# 555_project_555timer_ic_revA.net
KiCad netlist of a schematic drawn in EAGLE
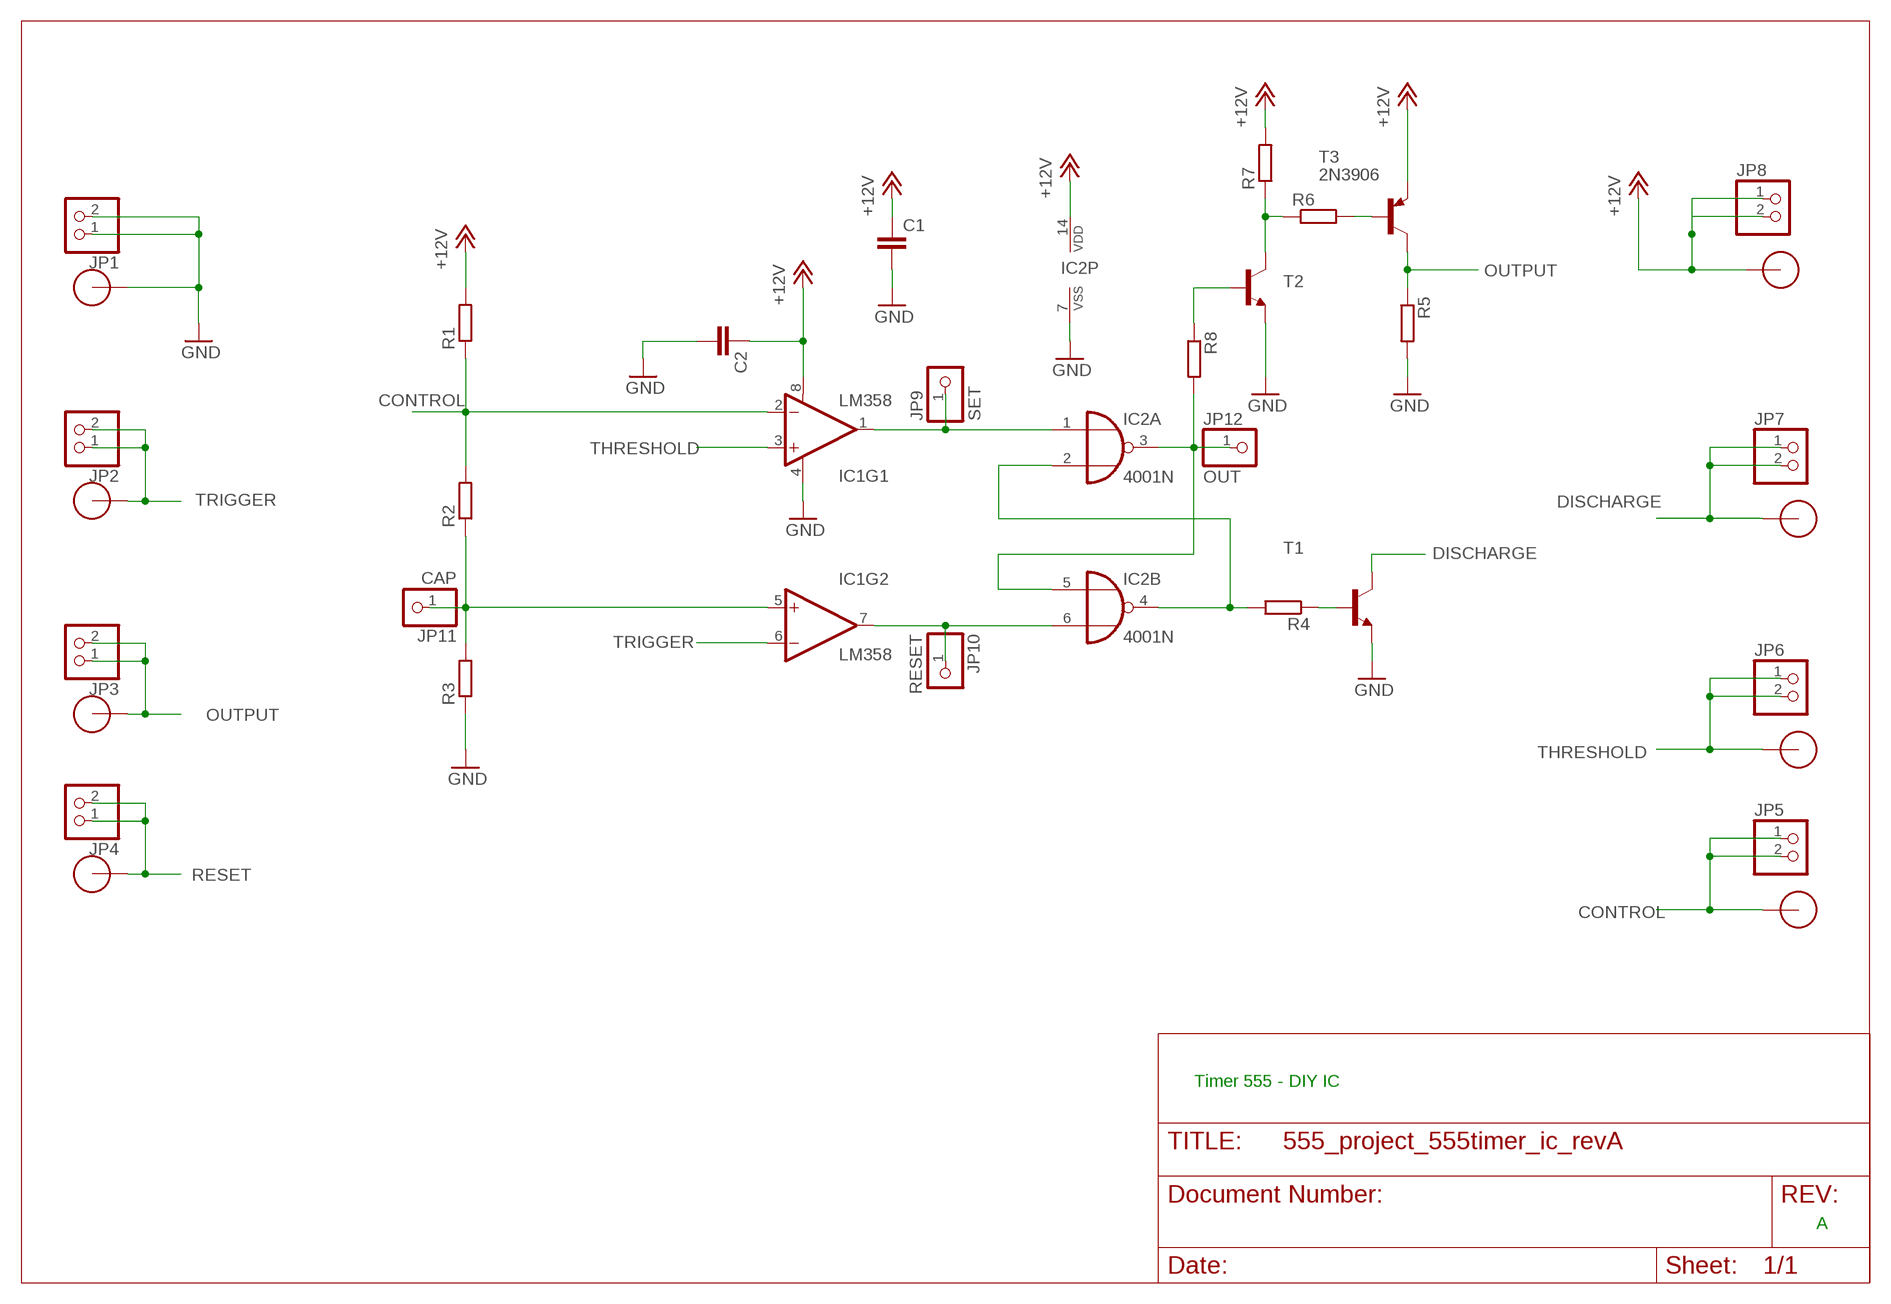
[diagram p0: schematic, sheet 1]

(export (version "E")
  (design (tool "Eeschema 10.0.6"))
  (components
    (comp (ref "C1")
      (value "C-EU025-024X044")
      (footprint "eagle-import:C025-024X044")
      (libsource (lib "eagle-import") (part "C-EU025-024X044"))
    )
    (comp (ref "C2")
      (value "C-EU025-024X044")
      (footprint "eagle-import:C025-024X044")
      (libsource (lib "eagle-import") (part "C-EU025-024X044"))
    )
    (comp (ref "IC1")
      (value "LM358")
      (footprint "eagle-import:DIP08")
      (libsource (lib "eagle-import") (part "LM358"))
    )
    (comp (ref "IC2")
      (value "4001N")
      (footprint "eagle-import:DIL14")
      (libsource (lib "eagle-import") (part "4001N"))
    )
    (comp (ref "JP1")
      (value "PINHD-1X2")
      (footprint "eagle-import:1X02")
      (libsource (lib "eagle-import") (part "PINHD-1X2"))
    )
    (comp (ref "JP2")
      (value "PINHD-1X2")
      (footprint "eagle-import:1X02")
      (libsource (lib "eagle-import") (part "PINHD-1X2"))
    )
    (comp (ref "JP3")
      (value "PINHD-1X2")
      (footprint "eagle-import:1X02")
      (libsource (lib "eagle-import") (part "PINHD-1X2"))
    )
    (comp (ref "JP4")
      (value "PINHD-1X2")
      (footprint "eagle-import:1X02")
      (libsource (lib "eagle-import") (part "PINHD-1X2"))
    )
    (comp (ref "JP5")
      (value "PINHD-1X2")
      (footprint "eagle-import:1X02")
      (libsource (lib "eagle-import") (part "PINHD-1X2"))
    )
    (comp (ref "JP6")
      (value "PINHD-1X2")
      (footprint "eagle-import:1X02")
      (libsource (lib "eagle-import") (part "PINHD-1X2"))
    )
    (comp (ref "JP7")
      (value "PINHD-1X2")
      (footprint "eagle-import:1X02")
      (libsource (lib "eagle-import") (part "PINHD-1X2"))
    )
    (comp (ref "JP8")
      (value "PINHD-1X2")
      (footprint "eagle-import:1X02")
      (libsource (lib "eagle-import") (part "PINHD-1X2"))
    )
    (comp (ref "JP9")
      (value "SET")
      (footprint "eagle-import:1X01")
      (libsource (lib "eagle-import") (part "PINHD-1X1"))
    )
    (comp (ref "JP10")
      (value "RESET")
      (footprint "eagle-import:1X01")
      (libsource (lib "eagle-import") (part "PINHD-1X1"))
    )
    (comp (ref "JP11")
      (value "CAP")
      (footprint "eagle-import:1X01")
      (libsource (lib "eagle-import") (part "PINHD-1X1"))
    )
    (comp (ref "JP12")
      (value "OUT")
      (footprint "eagle-import:1X01")
      (libsource (lib "eagle-import") (part "PINHD-1X1"))
    )
    (comp (ref "R1")
      (value "R-EU_0204/7")
      (footprint "eagle-import:0204_7")
      (libsource (lib "eagle-import") (part "R-EU_0204/7"))
    )
    (comp (ref "R2")
      (value "R-EU_0204/7")
      (footprint "eagle-import:0204_7")
      (libsource (lib "eagle-import") (part "R-EU_0204/7"))
    )
    (comp (ref "R3")
      (value "R-EU_0204/7")
      (footprint "eagle-import:0204_7")
      (libsource (lib "eagle-import") (part "R-EU_0204/7"))
    )
    (comp (ref "R4")
      (value "R-EU_0204/7")
      (footprint "eagle-import:0204_7")
      (libsource (lib "eagle-import") (part "R-EU_0204/7"))
    )
    (comp (ref "R5")
      (value "R-EU_0204/7")
      (footprint "eagle-import:0204_7")
      (libsource (lib "eagle-import") (part "R-EU_0204/7"))
    )
    (comp (ref "R6")
      (value "R-EU_0204/7")
      (footprint "eagle-import:0204_7")
      (libsource (lib "eagle-import") (part "R-EU_0204/7"))
    )
    (comp (ref "R7")
      (value "R-EU_0204/7")
      (footprint "eagle-import:0204_7")
      (libsource (lib "eagle-import") (part "R-EU_0204/7"))
    )
    (comp (ref "R8")
      (value "R-EU_0204/7")
      (footprint "eagle-import:0204_7")
      (libsource (lib "eagle-import") (part "R-EU_0204/7"))
    )
    (comp (ref "T1")
      (value "BC546-NPN-TO92-CBE")
      (footprint "eagle-import:TO92-CBE")
      (libsource (lib "eagle-import") (part "-NPN-TO92-CBEBC546"))
    )
    (comp (ref "T2")
      (value "TRANSISTOR_NPN2N3904")
      (footprint "eagle-import:TO-92")
      (libsource (lib "eagle-import") (part "TRANSISTOR_NPN2N3904"))
    )
    (comp (ref "T3")
      (value "2N3906")
      (footprint "eagle-import:TO92")
      (libsource (lib "eagle-import") (part "2N3906"))
    )
    (comp (ref "U$1")
      (value "ALLIGATOR_CLIP_PAD")
      (footprint "eagle-import:BIGTAP")
      (libsource (lib "eagle-import") (part "ALLIGATOR_CLIP_PAD"))
    )
    (comp (ref "U$3")
      (value "ALLIGATOR_CLIP_PAD")
      (footprint "eagle-import:BIGTAP")
      (libsource (lib "eagle-import") (part "ALLIGATOR_CLIP_PAD"))
    )
    (comp (ref "U$4")
      (value "ALLIGATOR_CLIP_PAD")
      (footprint "eagle-import:BIGTAP")
      (libsource (lib "eagle-import") (part "ALLIGATOR_CLIP_PAD"))
    )
    (comp (ref "U$5")
      (value "ALLIGATOR_CLIP_PAD")
      (footprint "eagle-import:BIGTAP")
      (libsource (lib "eagle-import") (part "ALLIGATOR_CLIP_PAD"))
    )
    (comp (ref "U$6")
      (value "ALLIGATOR_CLIP_PAD")
      (footprint "eagle-import:BIGTAP")
      (libsource (lib "eagle-import") (part "ALLIGATOR_CLIP_PAD"))
    )
    (comp (ref "U$7")
      (value "ALLIGATOR_CLIP_PAD")
      (footprint "eagle-import:BIGTAP")
      (libsource (lib "eagle-import") (part "ALLIGATOR_CLIP_PAD"))
    )
    (comp (ref "U$8")
      (value "ALLIGATOR_CLIP_PAD")
      (footprint "eagle-import:BIGTAP")
      (libsource (lib "eagle-import") (part "ALLIGATOR_CLIP_PAD"))
    )
    (comp (ref "U$9")
      (value "ALLIGATOR_CLIP_PAD")
      (footprint "eagle-import:BIGTAP")
      (libsource (lib "eagle-import") (part "ALLIGATOR_CLIP_PAD"))
    )
  )
  (nets
    (net (code "1") (name "+12V") (class "Default")
      (node (ref "C1") (pin "1") (pinfunction "1_1") (pintype "passive"))
      (node (ref "C2") (pin "1") (pinfunction "1_1") (pintype "passive"))
      (node (ref "IC1") (pin "8") (pinfunction "V+_8") (pintype "power_in"))
      (node (ref "IC2") (pin "14") (pinfunction "VDD_14") (pintype "power_in"))
      (node (ref "JP8") (pin "1") (pinfunction "1_1") (pintype "passive"))
      (node (ref "JP8") (pin "2") (pinfunction "2_2") (pintype "passive"))
      (node (ref "R1") (pin "2") (pinfunction "2_2") (pintype "passive"))
      (node (ref "R7") (pin "2") (pinfunction "2_2") (pintype "passive"))
      (node (ref "T3") (pin "3") (pinfunction "E_3") (pintype "passive"))
      (node (ref "U$7") (pin "P$1") (pinfunction "P$1_P$1") (pintype "bidirectional"))
    )
    (net (code "2") (name "/CONTROL") (class "Default")
      (node (ref "IC1") (pin "2") (pinfunction "-IN_2") (pintype "input"))
      (node (ref "JP5") (pin "1") (pinfunction "1_1") (pintype "passive"))
      (node (ref "JP5") (pin "2") (pinfunction "2_2") (pintype "passive"))
      (node (ref "R1") (pin "1") (pinfunction "1_1") (pintype "passive"))
      (node (ref "R2") (pin "2") (pinfunction "2_2") (pintype "passive"))
      (node (ref "U$1") (pin "P$1") (pinfunction "P$1_P$1") (pintype "bidirectional"))
    )
    (net (code "3") (name "/DISCHARGE") (class "Default")
      (node (ref "JP7") (pin "1") (pinfunction "1_1") (pintype "passive"))
      (node (ref "JP7") (pin "2") (pinfunction "2_2") (pintype "passive"))
      (node (ref "T1") (pin "C") (pinfunction "C_C") (pintype "passive"))
      (node (ref "U$8") (pin "P$1") (pinfunction "P$1_P$1") (pintype "bidirectional"))
    )
    (net (code "4") (name "/OUTPUT") (class "Default")
      (node (ref "JP3") (pin "1") (pinfunction "1_1") (pintype "passive"))
      (node (ref "JP3") (pin "2") (pinfunction "2_2") (pintype "passive"))
      (node (ref "R5") (pin "1") (pinfunction "1_1") (pintype "passive"))
      (node (ref "T3") (pin "1") (pinfunction "C_1") (pintype "passive"))
      (node (ref "U$5") (pin "P$1") (pinfunction "P$1_P$1") (pintype "bidirectional"))
    )
    (net (code "5") (name "/RESET") (class "Default")
      (node (ref "JP4") (pin "1") (pinfunction "1_1") (pintype "passive"))
      (node (ref "JP4") (pin "2") (pinfunction "2_2") (pintype "passive"))
      (node (ref "U$6") (pin "P$1") (pinfunction "P$1_P$1") (pintype "bidirectional"))
    )
    (net (code "6") (name "/THRESHOLD") (class "Default")
      (node (ref "IC1") (pin "3") (pinfunction "+IN_3") (pintype "input"))
      (node (ref "JP6") (pin "1") (pinfunction "1_1") (pintype "passive"))
      (node (ref "JP6") (pin "2") (pinfunction "2_2") (pintype "passive"))
      (node (ref "U$9") (pin "P$1") (pinfunction "P$1_P$1") (pintype "bidirectional"))
    )
    (net (code "7") (name "/TRIGGER") (class "Default")
      (node (ref "IC1") (pin "6") (pinfunction "-IN_6") (pintype "input"))
      (node (ref "JP2") (pin "1") (pinfunction "1_1") (pintype "passive"))
      (node (ref "JP2") (pin "2") (pinfunction "2_2") (pintype "passive"))
      (node (ref "U$4") (pin "P$1") (pinfunction "P$1_P$1") (pintype "bidirectional"))
    )
    (net (code "8") (name "GND") (class "Default")
      (node (ref "C1") (pin "2") (pinfunction "2_2") (pintype "passive"))
      (node (ref "C2") (pin "2") (pinfunction "2_2") (pintype "passive"))
      (node (ref "IC1") (pin "4") (pinfunction "V-_4") (pintype "power_in"))
      (node (ref "IC2") (pin "7") (pinfunction "VSS_7") (pintype "power_in"))
      (node (ref "JP1") (pin "1") (pinfunction "1_1") (pintype "passive"))
      (node (ref "JP1") (pin "2") (pinfunction "2_2") (pintype "passive"))
      (node (ref "R3") (pin "1") (pinfunction "1_1") (pintype "passive"))
      (node (ref "R5") (pin "2") (pinfunction "2_2") (pintype "passive"))
      (node (ref "T1") (pin "E") (pinfunction "E_E") (pintype "passive"))
      (node (ref "T2") (pin "1") (pinfunction "E_1") (pintype "passive"))
      (node (ref "U$3") (pin "P$1") (pinfunction "P$1_P$1") (pintype "bidirectional"))
    )
    (net (code "9") (name "Net-(IC1A-OUT)") (class "Default")
      (node (ref "IC1") (pin "1") (pinfunction "OUT_1") (pintype "output"))
      (node (ref "IC2") (pin "1") (pinfunction "I0_1") (pintype "input"))
      (node (ref "JP9") (pin "1") (pinfunction "1_1") (pintype "passive"))
    )
    (net (code "10") (name "Net-(IC1B-+IN)") (class "Default")
      (node (ref "IC1") (pin "5") (pinfunction "+IN_5") (pintype "input"))
      (node (ref "JP11") (pin "1") (pinfunction "1_1") (pintype "passive"))
      (node (ref "R2") (pin "1") (pinfunction "1_1") (pintype "passive"))
      (node (ref "R3") (pin "2") (pinfunction "2_2") (pintype "passive"))
    )
    (net (code "11") (name "Net-(IC1B-OUT)") (class "Default")
      (node (ref "IC1") (pin "7") (pinfunction "OUT_7") (pintype "output"))
      (node (ref "IC2") (pin "6") (pinfunction "I1_6") (pintype "input"))
      (node (ref "JP10") (pin "1") (pinfunction "1_1") (pintype "passive"))
    )
    (net (code "12") (name "Net-(IC2A-I1)") (class "Default")
      (node (ref "IC2") (pin "2") (pinfunction "I1_2") (pintype "input"))
      (node (ref "IC2") (pin "4") (pinfunction "O_4") (pintype "output"))
      (node (ref "R4") (pin "2") (pinfunction "2_2") (pintype "passive"))
    )
    (net (code "13") (name "Net-(IC2A-O)") (class "Default")
      (node (ref "IC2") (pin "3") (pinfunction "O_3") (pintype "output"))
      (node (ref "IC2") (pin "5") (pinfunction "I0_5") (pintype "input"))
      (node (ref "JP12") (pin "1") (pinfunction "1_1") (pintype "passive"))
      (node (ref "R8") (pin "2") (pinfunction "2_2") (pintype "passive"))
    )
    (net (code "14") (name "Net-(R4-Pad1)") (class "Default")
      (node (ref "R4") (pin "1") (pinfunction "1_1") (pintype "passive"))
      (node (ref "T1") (pin "B") (pinfunction "B_B") (pintype "passive"))
    )
    (net (code "15") (name "Net-(T2-B)") (class "Default")
      (node (ref "R8") (pin "1") (pinfunction "1_1") (pintype "passive"))
      (node (ref "T2") (pin "2") (pinfunction "B_2") (pintype "passive"))
    )
    (net (code "16") (name "Net-(T2-C)") (class "Default")
      (node (ref "R6") (pin "1") (pinfunction "1_1") (pintype "passive"))
      (node (ref "R7") (pin "1") (pinfunction "1_1") (pintype "passive"))
      (node (ref "T2") (pin "3") (pinfunction "C_3") (pintype "passive"))
    )
    (net (code "17") (name "Net-(T3-B)") (class "Default")
      (node (ref "R6") (pin "2") (pinfunction "2_2") (pintype "passive"))
      (node (ref "T3") (pin "2") (pinfunction "B_2") (pintype "passive"))
    )
  )
)
